# PCBDesign01.net
KiCad netlist of a schematic drawn in EAGLE
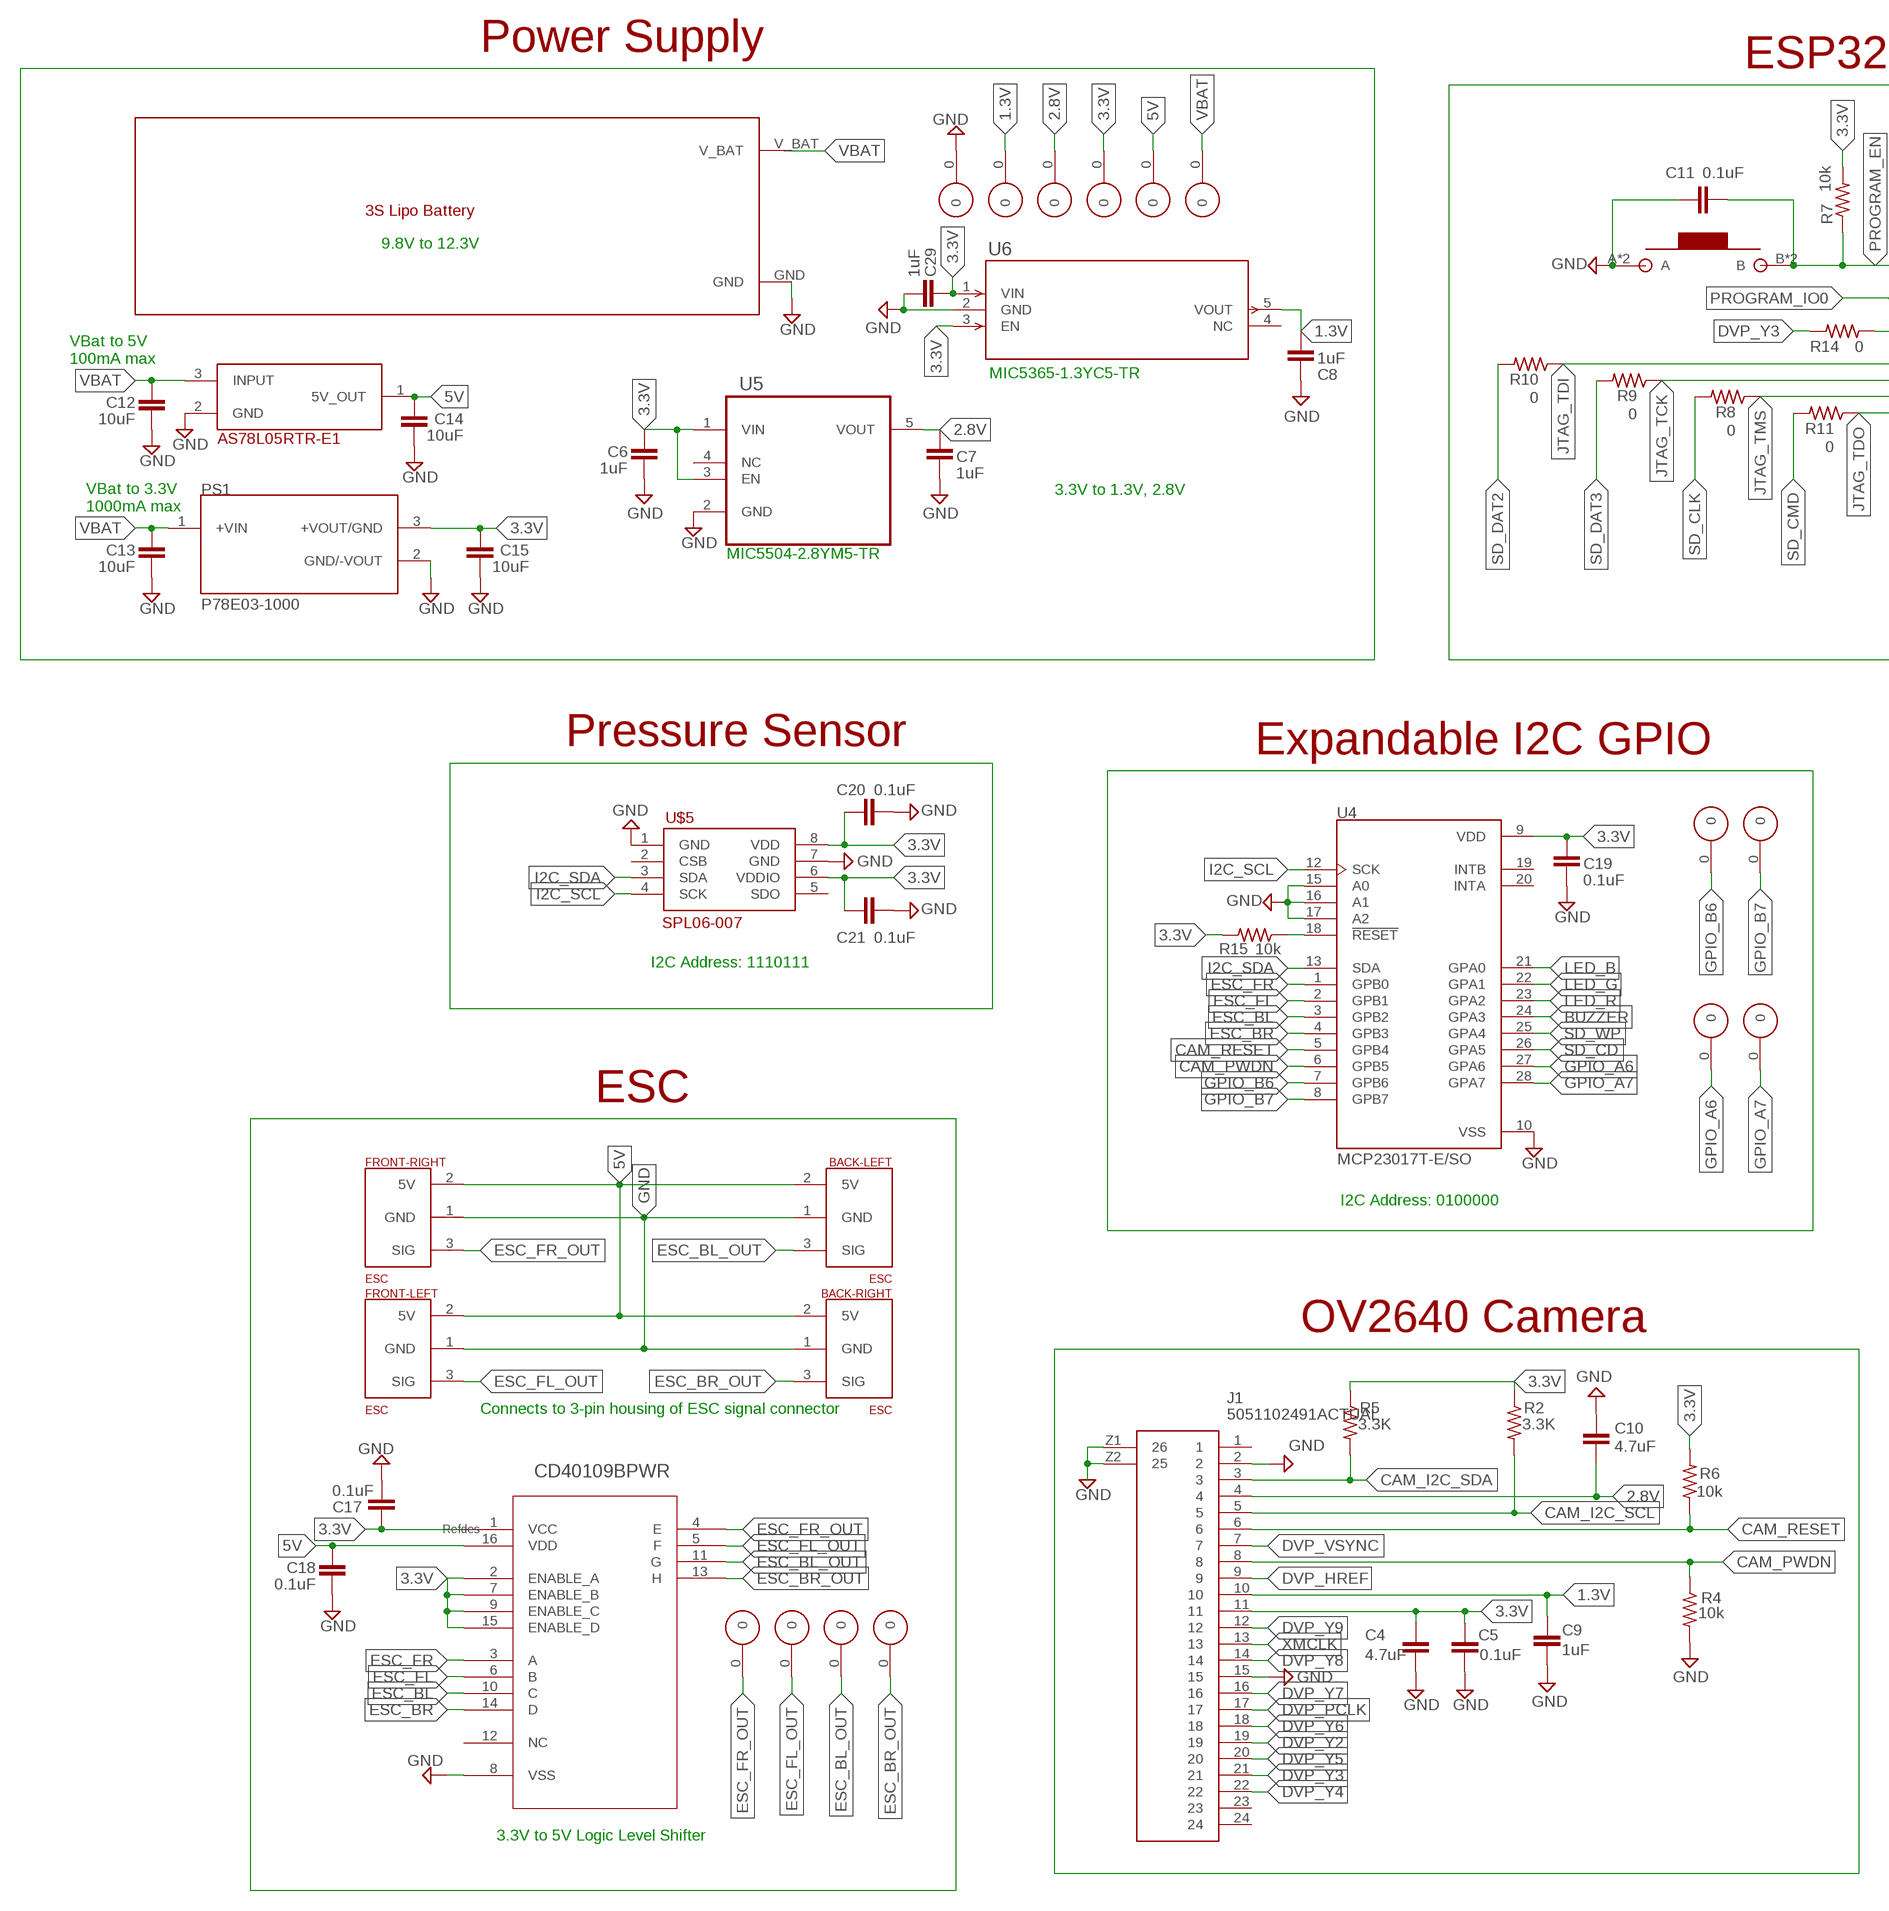
[diagram p0: schematic, sheet 1, part 1 of 2]
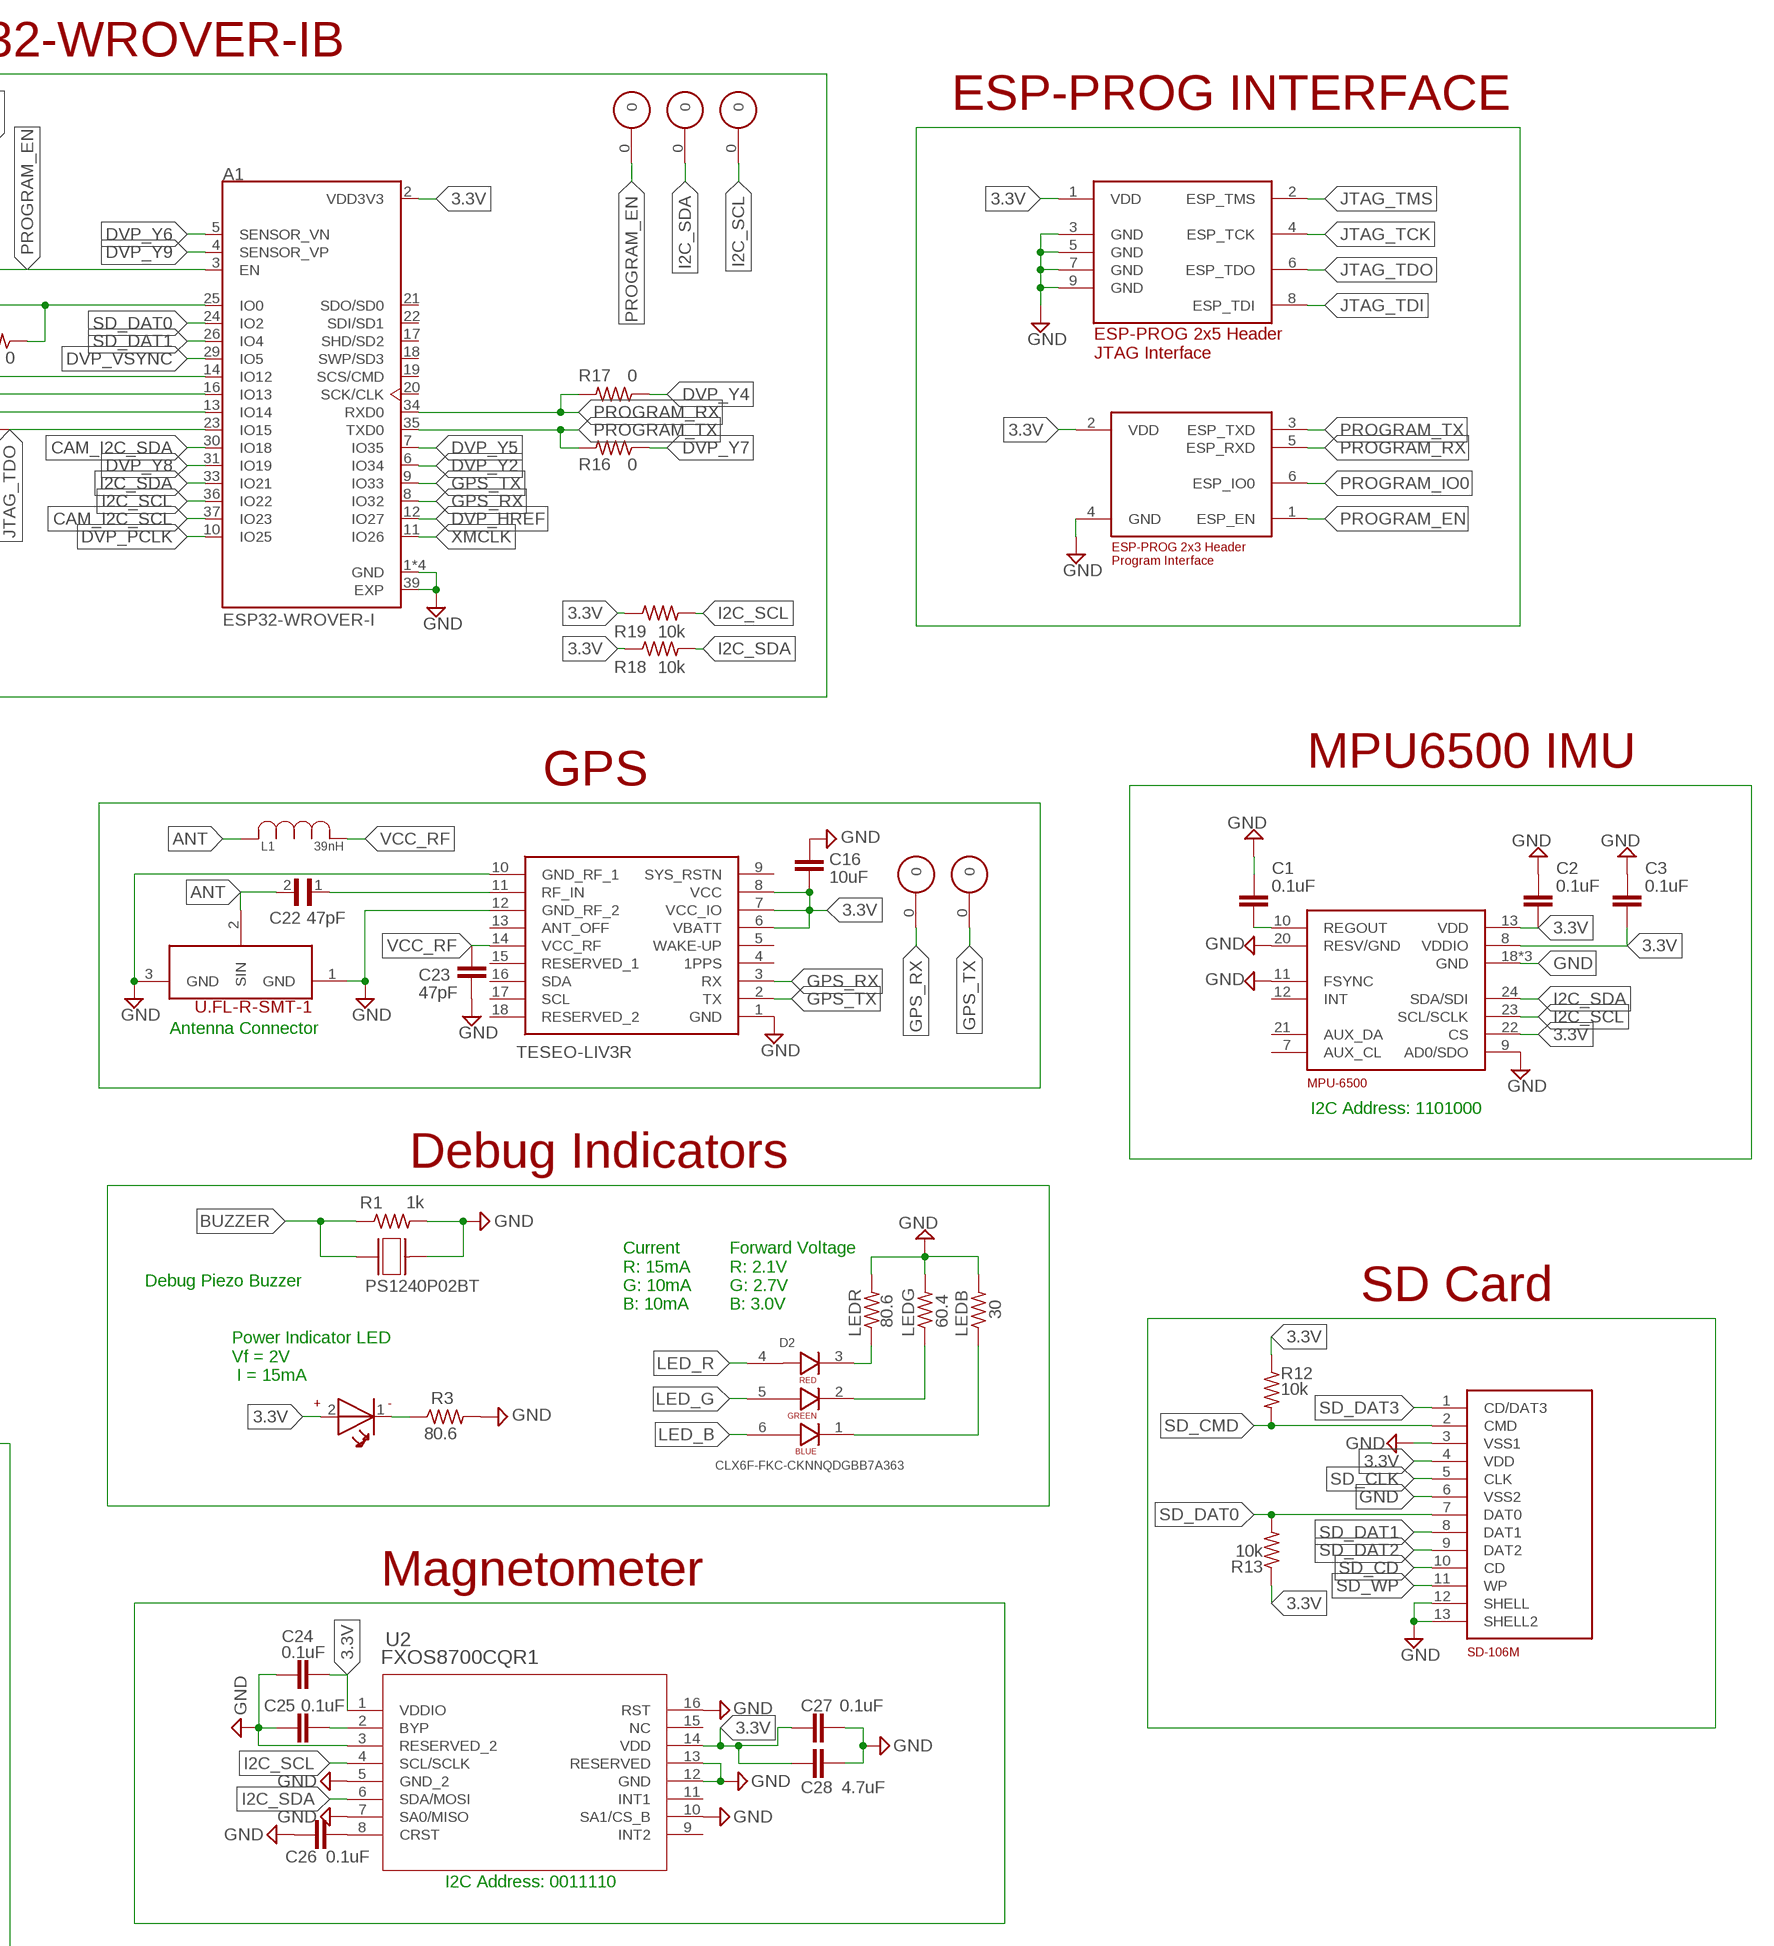
[diagram p1: schematic, sheet 1, part 2 of 2]

(export (version "E")
  (design (tool "Eeschema 10.0.6"))
  (components
    (comp (ref "A1")
      (value "ESP32-WROVER-I")
      (footprint "eagle-import:XCVR_ESP32-WROVER-I")
      (fields (field (name "MF") "Espressif Systems"))
      (libsource (lib "eagle-import") (part "ESP32-WROVER-I"))
    )
    (comp (ref "BACK-LEFT")
      (value "ESC")
      (footprint "eagle-import:MA03-1")
      (libsource (lib "eagle-import") (part "ESC"))
    )
    (comp (ref "BACK-RIGHT")
      (value "ESC")
      (footprint "eagle-import:MA03-1")
      (libsource (lib "eagle-import") (part "ESC"))
    )
    (comp (ref "BUZZER")
      (value "PS1240P02BT")
      (footprint "eagle-import:XDCR_PS1240P02BT")
      (fields (field (name "DIGI-KEY_PART_NUMBER") "445-2525-1-ND") (field (name "MF") "TDK"))
      (libsource (lib "eagle-import") (part "PS1240P02BT"))
    )
    (comp (ref "C1")
      (value "0.1uF")
      (footprint "eagle-import:CAPC2012X110")
      (libsource (lib "eagle-import") (part "CCHIP-0805(2012-METRIC)_"))
    )
    (comp (ref "C2")
      (value "0.1uF")
      (footprint "eagle-import:CAPC2012X110")
      (libsource (lib "eagle-import") (part "CCHIP-0805(2012-METRIC)_"))
    )
    (comp (ref "C3")
      (value "0.1uF")
      (footprint "eagle-import:CAPC2012X110")
      (libsource (lib "eagle-import") (part "CCHIP-0805(2012-METRIC)_"))
    )
    (comp (ref "C4")
      (value "4.7uF")
      (footprint "eagle-import:CAPC2012X110")
      (libsource (lib "eagle-import") (part "CCHIP-0805(2012-METRIC)_"))
    )
    (comp (ref "C5")
      (value "0.1uF")
      (footprint "eagle-import:CAPC2012X110")
      (libsource (lib "eagle-import") (part "CCHIP-0805(2012-METRIC)_"))
    )
    (comp (ref "C6")
      (value "1uF")
      (footprint "eagle-import:CAPC2012X110")
      (libsource (lib "eagle-import") (part "CCHIP-0805(2012-METRIC)_"))
    )
    (comp (ref "C7")
      (value "1uF")
      (footprint "eagle-import:CAPC2012X110")
      (libsource (lib "eagle-import") (part "CCHIP-0805(2012-METRIC)_"))
    )
    (comp (ref "C8")
      (value "1uF")
      (footprint "eagle-import:CAPC2012X110")
      (libsource (lib "eagle-import") (part "CCHIP-0805(2012-METRIC)_"))
    )
    (comp (ref "C9")
      (value "1uF")
      (footprint "eagle-import:CAPC2012X110")
      (libsource (lib "eagle-import") (part "CCHIP-0805(2012-METRIC)_"))
    )
    (comp (ref "C10")
      (value "4.7uF")
      (footprint "eagle-import:CAPC2012X110")
      (libsource (lib "eagle-import") (part "CCHIP-0805(2012-METRIC)_"))
    )
    (comp (ref "C11")
      (value "0.1uF")
      (footprint "eagle-import:CAPC2012X110")
      (libsource (lib "eagle-import") (part "CCHIP-0805(2012-METRIC)_"))
    )
    (comp (ref "C12")
      (value "10uF")
      (footprint "eagle-import:CAPC2012X110")
      (libsource (lib "eagle-import") (part "CCHIP-0805(2012-METRIC)_"))
    )
    (comp (ref "C13")
      (value "10uF")
      (footprint "eagle-import:CAPC2012X110")
      (libsource (lib "eagle-import") (part "CCHIP-0805(2012-METRIC)_"))
    )
    (comp (ref "C14")
      (value "10uF")
      (footprint "eagle-import:CAPC2012X110")
      (libsource (lib "eagle-import") (part "CCHIP-0805(2012-METRIC)_"))
    )
    (comp (ref "C15")
      (value "10uF")
      (footprint "eagle-import:CAPC2012X110")
      (libsource (lib "eagle-import") (part "CCHIP-0805(2012-METRIC)_"))
    )
    (comp (ref "C16")
      (value "10uF")
      (footprint "eagle-import:CAPC2012X110")
      (libsource (lib "eagle-import") (part "CCHIP-0805(2012-METRIC)_"))
    )
    (comp (ref "C17")
      (value "0.1uF")
      (footprint "eagle-import:CAPC2012X110")
      (libsource (lib "eagle-import") (part "CCHIP-0805(2012-METRIC)_"))
    )
    (comp (ref "C18")
      (value "0.1uF")
      (footprint "eagle-import:CAPC2012X110")
      (libsource (lib "eagle-import") (part "CCHIP-0805(2012-METRIC)_"))
    )
    (comp (ref "C19")
      (value "0.1uF")
      (footprint "eagle-import:CAPC2012X110")
      (libsource (lib "eagle-import") (part "CCHIP-0805(2012-METRIC)_"))
    )
    (comp (ref "C20")
      (value "0.1uF")
      (footprint "eagle-import:CAPC2012X110")
      (libsource (lib "eagle-import") (part "CCHIP-0805(2012-METRIC)_"))
    )
    (comp (ref "C21")
      (value "0.1uF")
      (footprint "eagle-import:CAPC2012X110")
      (libsource (lib "eagle-import") (part "CCHIP-0805(2012-METRIC)_"))
    )
    (comp (ref "C22")
      (value "47pF")
      (footprint "eagle-import:CAPC1005X55N")
      (fields
        (field (name "DIGI-KEY_PART_NUMBER") "399-7796-1-ND")
        (field (name "MF") "KEMET")
        (field (name "MP") "C0402C470K5GACTU")
      )
      (libsource (lib "eagle-import") (part "C0402C470K5GACTU"))
    )
    (comp (ref "C23")
      (value "47pF")
      (footprint "eagle-import:CAPC2012X110")
      (libsource (lib "eagle-import") (part "CCHIP-0805(2012-METRIC)_"))
    )
    (comp (ref "C24")
      (value "0.1uF")
      (footprint "eagle-import:CAPC2012X110")
      (libsource (lib "eagle-import") (part "CCHIP-0805(2012-METRIC)_"))
    )
    (comp (ref "C25")
      (value "0.1uF")
      (footprint "eagle-import:CAPC2012X110")
      (libsource (lib "eagle-import") (part "CCHIP-0805(2012-METRIC)_"))
    )
    (comp (ref "C26")
      (value "0.1uF")
      (footprint "eagle-import:CAPC2012X110")
      (libsource (lib "eagle-import") (part "CCHIP-0805(2012-METRIC)_"))
    )
    (comp (ref "C27")
      (value "0.1uF")
      (footprint "eagle-import:CAPC2012X110")
      (libsource (lib "eagle-import") (part "CCHIP-0805(2012-METRIC)_"))
    )
    (comp (ref "C28")
      (value "4.7uF")
      (footprint "eagle-import:CAPC2012X110")
      (libsource (lib "eagle-import") (part "CCHIP-0805(2012-METRIC)_"))
    )
    (comp (ref "C29")
      (value "1uF")
      (footprint "eagle-import:CAPC2012X110")
      (libsource (lib "eagle-import") (part "CCHIP-0805(2012-METRIC)_"))
    )
    (comp (ref "D2")
      (value "CLX6F-FKC-CKNNQDGBB7A363")
      (footprint "eagle-import:SOJ100P350X290-6N")
      (fields (field (name "MF") "Cree Inc."))
      (libsource (lib "eagle-import") (part "CLX6F-FKC-CKNNQDGBB7A363"))
    )
    (comp (ref "FRONT-LEFT")
      (value "ESC")
      (footprint "eagle-import:MA03-1")
      (libsource (lib "eagle-import") (part "ESC"))
    )
    (comp (ref "FRONT-RIGHT")
      (value "ESC")
      (footprint "eagle-import:MA03-1")
      (libsource (lib "eagle-import") (part "ESC"))
    )
    (comp (ref "IC1")
      (value "TESEO-LIV3R")
      (footprint "eagle-import:TESEOLIV3R")
      (fields (field (name "MOUSER_PART_NUMBER") "511-TESEO-LIV3R"))
      (libsource (lib "eagle-import") (part "TESEO-LIV3R"))
    )
    (comp (ref "J1")
      (value "5051102491ACTUAL")
      (footprint "eagle-import:687124149022")
      (libsource (lib "eagle-import") (part "5051102491ACTUAL"))
    )
    (comp (ref "L1")
      (value "39nH")
      (footprint "eagle-import:IND0402_22N_TAI_TAY-M")
      (fields (field (name "MANUFACTURER_PART_NUMBER") "HK100539NJ-T"))
      (libsource (lib "eagle-import") (part "HK100539NJ-TIND0402_22N_TAI_TAY-M"))
    )
    (comp (ref "LEDB")
      (value "30")
      (footprint "eagle-import:RESC2012X65")
      (libsource (lib "eagle-import") (part "R-USCHIP-0805(2012-METRIC)_"))
    )
    (comp (ref "LEDG")
      (value "60.4")
      (footprint "eagle-import:RESC2012X65")
      (libsource (lib "eagle-import") (part "R-USCHIP-0805(2012-METRIC)_"))
    )
    (comp (ref "LEDR")
      (value "80.6")
      (footprint "eagle-import:RESC2012X65")
      (libsource (lib "eagle-import") (part "R-USCHIP-0805(2012-METRIC)_"))
    )
    (comp (ref "PS1")
      (value "P78E03-1000")
      (footprint "eagle-import:CONV_P78E03-1000")
      (fields (field (name "MANUFACTURER") "CUI Inc"))
      (libsource (lib "eagle-import") (part "P78E03-1000"))
    )
    (comp (ref "PWR-INDICATOR")
      (value "WL-SMCW-150060GS75000-G")
      (footprint "eagle-import:WL-SMCW_0603")
      (fields (field (name "MF") "Wurth Electronics") (field (name "MP") "150060VS75000"))
      (libsource (lib "eagle-import") (part "WL-SMCW-150060GS75000-G"))
    )
    (comp (ref "R1")
      (value "1k")
      (footprint "eagle-import:RESC2012X65")
      (libsource (lib "eagle-import") (part "R-USCHIP-0805(2012-METRIC)_"))
    )
    (comp (ref "R2")
      (value "3.3K")
      (footprint "eagle-import:RESC2012X65")
      (libsource (lib "eagle-import") (part "R-USCHIP-0805(2012-METRIC)_"))
    )
    (comp (ref "R3")
      (value "80.6")
      (footprint "eagle-import:RESC2012X65")
      (libsource (lib "eagle-import") (part "R-USCHIP-0805(2012-METRIC)_"))
    )
    (comp (ref "R4")
      (value "10k")
      (footprint "eagle-import:RESC2012X65")
      (libsource (lib "eagle-import") (part "R-USCHIP-0805(2012-METRIC)_"))
    )
    (comp (ref "R5")
      (value "3.3K")
      (footprint "eagle-import:RESC2012X65")
      (libsource (lib "eagle-import") (part "R-USCHIP-0805(2012-METRIC)_"))
    )
    (comp (ref "R6")
      (value "10k")
      (footprint "eagle-import:RESC2012X65")
      (libsource (lib "eagle-import") (part "R-USCHIP-0805(2012-METRIC)_"))
    )
    (comp (ref "R7")
      (value "10k")
      (footprint "eagle-import:RESC2012X65")
      (libsource (lib "eagle-import") (part "R-USCHIP-0805(2012-METRIC)_"))
    )
    (comp (ref "R8")
      (value "0")
      (footprint "eagle-import:RESC2012X65")
      (libsource (lib "eagle-import") (part "R-USCHIP-0805(2012-METRIC)_"))
    )
    (comp (ref "R9")
      (value "0")
      (footprint "eagle-import:RESC2012X65")
      (libsource (lib "eagle-import") (part "R-USCHIP-0805(2012-METRIC)_"))
    )
    (comp (ref "R10")
      (value "0")
      (footprint "eagle-import:RESC2012X65")
      (libsource (lib "eagle-import") (part "R-USCHIP-0805(2012-METRIC)_"))
    )
    (comp (ref "R11")
      (value "0")
      (footprint "eagle-import:RESC2012X65")
      (libsource (lib "eagle-import") (part "R-USCHIP-0805(2012-METRIC)_"))
    )
    (comp (ref "R12")
      (value "10k")
      (footprint "eagle-import:RESC2012X65")
      (libsource (lib "eagle-import") (part "R-USCHIP-0805(2012-METRIC)_"))
    )
    (comp (ref "R13")
      (value "10k")
      (footprint "eagle-import:RESC2012X65")
      (libsource (lib "eagle-import") (part "R-USCHIP-0805(2012-METRIC)_"))
    )
    (comp (ref "R14")
      (value "0")
      (footprint "eagle-import:RESC2012X65")
      (libsource (lib "eagle-import") (part "R-USCHIP-0805(2012-METRIC)_"))
    )
    (comp (ref "R15")
      (value "10k")
      (footprint "eagle-import:RESC2012X65")
      (libsource (lib "eagle-import") (part "R-USCHIP-0805(2012-METRIC)_"))
    )
    (comp (ref "R16")
      (value "0")
      (footprint "eagle-import:RESC2012X65")
      (libsource (lib "eagle-import") (part "R-USCHIP-0805(2012-METRIC)_"))
    )
    (comp (ref "R17")
      (value "0")
      (footprint "eagle-import:RESC2012X65")
      (libsource (lib "eagle-import") (part "R-USCHIP-0805(2012-METRIC)_"))
    )
    (comp (ref "R18")
      (value "10k")
      (footprint "eagle-import:RESC2012X65")
      (libsource (lib "eagle-import") (part "R-USCHIP-0805(2012-METRIC)_"))
    )
    (comp (ref "R19")
      (value "10k")
      (footprint "eagle-import:RESC2012X65")
      (libsource (lib "eagle-import") (part "R-USCHIP-0805(2012-METRIC)_"))
    )
    (comp (ref "U$1")
      (value "MPU6500")
      (footprint "eagle-import:QFN40P300X300X105-24N")
      (libsource (lib "eagle-import") (part "MPU6500"))
    )
    (comp (ref "U$2")
      (value "TESTPOINT")
      (footprint "eagle-import:TESTPOINT")
      (libsource (lib "eagle-import") (part "TESTPOINT"))
    )
    (comp (ref "U$3")
      (value "SD-106M")
      (footprint "eagle-import:SDCARD")
      (libsource (lib "eagle-import") (part "SD-106M"))
    )
    (comp (ref "U$4")
      (value "U.FL-R-SMT-1")
      (footprint "eagle-import:U.FL")
      (libsource (lib "eagle-import") (part "U.FL-R-SMT-1"))
    )
    (comp (ref "U$5")
      (value "SPL06-007")
      (footprint "eagle-import:SPL06-007")
      (libsource (lib "eagle-import") (part "SPL06-007"))
    )
    (comp (ref "U$6")
      (value "ESP-PROG_JTAG_HEADER")
      (footprint "eagle-import:SAMTEC-FTS-105-01-X-D")
      (libsource (lib "eagle-import") (part "ESP-PROG_JTAG_HEADER"))
    )
    (comp (ref "U$7")
      (value "ESP-PROG_PROGRAM_HEADER")
      (footprint "eagle-import:SAMTEC-FTS-103-01-X-D")
      (libsource (lib "eagle-import") (part "ESP-PROG_PROGRAM_HEADER"))
    )
    (comp (ref "U$8")
      (value "RESET")
      (footprint "eagle-import:BUTTON")
      (libsource (lib "eagle-import") (part "BUTTON"))
    )
    (comp (ref "U$9")
      (value "TESTPOINT")
      (footprint "eagle-import:TESTPOINT")
      (libsource (lib "eagle-import") (part "TESTPOINT"))
    )
    (comp (ref "U$10")
      (value "TESTPOINT")
      (footprint "eagle-import:TESTPOINT")
      (libsource (lib "eagle-import") (part "TESTPOINT"))
    )
    (comp (ref "U$11")
      (value "TESTPOINT")
      (footprint "eagle-import:TESTPOINT")
      (libsource (lib "eagle-import") (part "TESTPOINT"))
    )
    (comp (ref "U$12")
      (value "TESTPOINT")
      (footprint "eagle-import:TESTPOINT")
      (libsource (lib "eagle-import") (part "TESTPOINT"))
    )
    (comp (ref "U$13")
      (value "TESTPOINT")
      (footprint "eagle-import:TESTPOINT")
      (libsource (lib "eagle-import") (part "TESTPOINT"))
    )
    (comp (ref "U$14")
      (value "TESTPOINT")
      (footprint "eagle-import:TESTPOINT")
      (libsource (lib "eagle-import") (part "TESTPOINT"))
    )
    (comp (ref "U$15")
      (value "TESTPOINT")
      (footprint "eagle-import:TESTPOINT")
      (libsource (lib "eagle-import") (part "TESTPOINT"))
    )
    (comp (ref "U$16")
      (value "TESTPOINT")
      (footprint "eagle-import:TESTPOINT")
      (libsource (lib "eagle-import") (part "TESTPOINT"))
    )
    (comp (ref "U$17")
      (value "TESTPOINT")
      (footprint "eagle-import:TESTPOINT")
      (libsource (lib "eagle-import") (part "TESTPOINT"))
    )
    (comp (ref "U$18")
      (value "TESTPOINT")
      (footprint "eagle-import:TESTPOINT")
      (libsource (lib "eagle-import") (part "TESTPOINT"))
    )
    (comp (ref "U$19")
      (value "TESTPOINT")
      (footprint "eagle-import:TESTPOINT")
      (libsource (lib "eagle-import") (part "TESTPOINT"))
    )
    (comp (ref "U$20")
      (value "TESTPOINT")
      (footprint "eagle-import:TESTPOINT")
      (libsource (lib "eagle-import") (part "TESTPOINT"))
    )
    (comp (ref "U$21")
      (value "TESTPOINT")
      (footprint "eagle-import:TESTPOINT")
      (libsource (lib "eagle-import") (part "TESTPOINT"))
    )
    (comp (ref "U$23")
      (value "TESTPOINT")
      (footprint "eagle-import:TESTPOINT")
      (libsource (lib "eagle-import") (part "TESTPOINT"))
    )
    (comp (ref "U$24")
      (value "TESTPOINT")
      (footprint "eagle-import:TESTPOINT")
      (libsource (lib "eagle-import") (part "TESTPOINT"))
    )
    (comp (ref "U$25")
      (value "TESTPOINT")
      (footprint "eagle-import:TESTPOINT")
      (libsource (lib "eagle-import") (part "TESTPOINT"))
    )
    (comp (ref "U$26")
      (value "TESTPOINT")
      (footprint "eagle-import:TESTPOINT")
      (libsource (lib "eagle-import") (part "TESTPOINT"))
    )
    (comp (ref "U$27")
      (value "TESTPOINT")
      (footprint "eagle-import:TESTPOINT")
      (libsource (lib "eagle-import") (part "TESTPOINT"))
    )
    (comp (ref "U$28")
      (value "AS78L05RTR-E1")
      (footprint "eagle-import:VREG_AP2204RA-3.3TRG1")
      (libsource (lib "eagle-import") (part "AS78L05RTR-E1"))
    )
    (comp (ref "U$29")
      (value "LARGE_BATTERY")
      (footprint "eagle-import:LARGE_BATTERY")
      (libsource (lib "eagle-import") (part "LARGE_BATTERY"))
    )
    (comp (ref "U2")
      (value "FXOS8700CQR1")
      (footprint "eagle-import:QFN16_3X3_NXP")
      (fields (field (name "COPYRIGHT") "Copyright (C) 2018 Accelerated Designs. All rights reserved"))
      (libsource (lib "eagle-import") (part "FXOS8700CQR1"))
    )
    (comp (ref "U3")
      (value "CD40109BPWR")
      (footprint "eagle-import:SOP65P640X120-16N")
      (fields (field (name "DIGI-KEY_PART_NUMBER") "296-12163-1-ND") (field (name "MF") "Texas Instruments"))
      (libsource (lib "eagle-import") (part "CD40109BPWR"))
    )
    (comp (ref "U4")
      (value "MCP23017T-E/SO")
      (footprint "eagle-import:SOIC127P1030X265-28N")
      (fields (field (name "DIGI-KEY_PART_NUMBER") "MCP23017T-E/SOCT-ND") (field (name "MF") "Microchip"))
      (libsource (lib "eagle-import") (part "MCP23017T-E/SO"))
    )
    (comp (ref "U5")
      (value "MIC5504-2.8YM5-TR")
      (footprint "eagle-import:SOT95P280X145-5N")
      (fields (field (name "MF") "Texas Instruments") (field (name "MP") "TPS61097-33DBVR"))
      (libsource (lib "eagle-import") (part "MIC5504-2.8YM5-TR"))
    )
    (comp (ref "U6")
      (value "MIC5365-1.3YC5-TRSC-70_C5_MCH-M")
      (footprint "eagle-import:SC-70_C5_MCH-M")
      (fields
        (field (name "MANUFACTURER_PART_NUMBER") "MIC5365-1.3YC5-TR")
        (field (name "COPYRIGHT") "Copyright (C) 2018 Accelerated Designs. All rights reserved")
      )
      (libsource (lib "eagle-import") (part "MIC5365-1.3YC5-TRSC-70_C5_MCH-M"))
    )
  )
  (nets
    (net (code "1") (name "1.3V") (class "Default")
      (node (ref "C8") (pin "1") (pinfunction "1_1") (pintype "passive"))
      (node (ref "C9") (pin "2") (pinfunction "2_2") (pintype "passive"))
      (node (ref "J1") (pin "10") (pinfunction "10_10") (pintype "bidirectional"))
      (node (ref "U$17") (pin "0") (pinfunction "0_0") (pintype "bidirectional"))
      (node (ref "U6") (pin "5") (pinfunction "VOUT_5") (pintype "output"))
    )
    (net (code "2") (name "2.8V") (class "Default")
      (node (ref "C10") (pin "1") (pinfunction "1_1") (pintype "passive"))
      (node (ref "C7") (pin "1") (pinfunction "1_1") (pintype "passive"))
      (node (ref "J1") (pin "4") (pinfunction "4_4") (pintype "bidirectional"))
      (node (ref "U$18") (pin "0") (pinfunction "0_0") (pintype "bidirectional"))
      (node (ref "U5") (pin "5") (pinfunction "VOUT_5") (pintype "output"))
    )
    (net (code "3") (name "3.3V") (class "Default")
      (node (ref "A1") (pin "2") (pinfunction "VDD3V3_2") (pintype "power_in"))
      (node (ref "C15") (pin "2") (pinfunction "2_2") (pintype "passive"))
      (node (ref "C16") (pin "2") (pinfunction "2_2") (pintype "passive"))
      (node (ref "C17") (pin "2") (pinfunction "2_2") (pintype "passive"))
      (node (ref "C19") (pin "2") (pinfunction "2_2") (pintype "passive"))
      (node (ref "C2") (pin "2") (pinfunction "2_2") (pintype "passive"))
      (node (ref "C20") (pin "2") (pinfunction "2_2") (pintype "passive"))
      (node (ref "C21") (pin "2") (pinfunction "2_2") (pintype "passive"))
      (node (ref "C24") (pin "2") (pinfunction "2_2") (pintype "passive"))
      (node (ref "C27") (pin "1") (pinfunction "1_1") (pintype "passive"))
      (node (ref "C28") (pin "1") (pinfunction "1_1") (pintype "passive"))
      (node (ref "C29") (pin "1") (pinfunction "1_1") (pintype "passive"))
      (node (ref "C3") (pin "2") (pinfunction "2_2") (pintype "passive"))
      (node (ref "C4") (pin "1") (pinfunction "1_1") (pintype "passive"))
      (node (ref "C5") (pin "1") (pinfunction "1_1") (pintype "passive"))
      (node (ref "C6") (pin "1") (pinfunction "1_1") (pintype "passive"))
      (node (ref "IC1") (pin "6") (pinfunction "VBATT_6") (pintype "bidirectional"))
      (node (ref "IC1") (pin "7") (pinfunction "VCC_IO_7") (pintype "bidirectional"))
      (node (ref "IC1") (pin "8") (pinfunction "VCC_8") (pintype "bidirectional"))
      (node (ref "J1") (pin "11") (pinfunction "11_11") (pintype "bidirectional"))
      (node (ref "PS1") (pin "3") (pinfunction "+VOUT/GND_3") (pintype "power_in"))
      (node (ref "PWR-INDICATOR") (pin "2") (pinfunction "+_2") (pintype "bidirectional"))
      (node (ref "R12") (pin "1") (pinfunction "1_1") (pintype "passive"))
      (node (ref "R13") (pin "1") (pinfunction "1_1") (pintype "passive"))
      (node (ref "R15") (pin "2") (pinfunction "2_2") (pintype "passive"))
      (node (ref "R18") (pin "1") (pinfunction "1_1") (pintype "passive"))
      (node (ref "R19") (pin "1") (pinfunction "1_1") (pintype "passive"))
      (node (ref "R2") (pin "1") (pinfunction "1_1") (pintype "passive"))
      (node (ref "R5") (pin "1") (pinfunction "1_1") (pintype "passive"))
      (node (ref "R6") (pin "2") (pinfunction "2_2") (pintype "passive"))
      (node (ref "R7") (pin "2") (pinfunction "2_2") (pintype "passive"))
      (node (ref "U$1") (pin "13") (pinfunction "VDD_13") (pintype "bidirectional"))
      (node (ref "U$1") (pin "22") (pinfunction "CS_22") (pintype "bidirectional"))
      (node (ref "U$1") (pin "8") (pinfunction "VDDIO_8") (pintype "bidirectional"))
      (node (ref "U$15") (pin "0") (pinfunction "0_0") (pintype "bidirectional"))
      (node (ref "U$3") (pin "4") (pinfunction "VDD_4") (pintype "bidirectional"))
      (node (ref "U$5") (pin "6") (pinfunction "VDDIO_6") (pintype "bidirectional"))
      (node (ref "U$5") (pin "8") (pinfunction "VDD_8") (pintype "bidirectional"))
      (node (ref "U$6") (pin "1") (pinfunction "VDD_1") (pintype "bidirectional"))
      (node (ref "U$7") (pin "2") (pinfunction "VDD_2") (pintype "bidirectional"))
      (node (ref "U2") (pin "1") (pinfunction "VDDIO_1") (pintype "power_in"))
      (node (ref "U2") (pin "14") (pinfunction "VDD_14") (pintype "power_in"))
      (node (ref "U3") (pin "1") (pinfunction "VCC_1") (pintype "power_in"))
      (node (ref "U3") (pin "15") (pinfunction "ENABLE_D_15") (pintype "input"))
      (node (ref "U3") (pin "2") (pinfunction "ENABLE_A_2") (pintype "input"))
      (node (ref "U3") (pin "7") (pinfunction "ENABLE_B_7") (pintype "input"))
      (node (ref "U3") (pin "9") (pinfunction "ENABLE_C_9") (pintype "input"))
      (node (ref "U4") (pin "9") (pinfunction "VDD_9") (pintype "power_in"))
      (node (ref "U5") (pin "1") (pinfunction "VIN_1") (pintype "power_in"))
      (node (ref "U5") (pin "3") (pinfunction "EN_3") (pintype "input"))
      (node (ref "U6") (pin "1") (pinfunction "VIN_1") (pintype "input"))
      (node (ref "U6") (pin "3") (pinfunction "EN_3") (pintype "input"))
    )
    (net (code "4") (name "5V") (class "Default")
      (node (ref "BACK-LEFT") (pin "2") (pinfunction "5V_2") (pintype "bidirectional"))
      (node (ref "BACK-RIGHT") (pin "2") (pinfunction "5V_2") (pintype "bidirectional"))
      (node (ref "C14") (pin "2") (pinfunction "2_2") (pintype "passive"))
      (node (ref "C18") (pin "2") (pinfunction "2_2") (pintype "passive"))
      (node (ref "FRONT-LEFT") (pin "2") (pinfunction "5V_2") (pintype "bidirectional"))
      (node (ref "FRONT-RIGHT") (pin "2") (pinfunction "5V_2") (pintype "bidirectional"))
      (node (ref "U$16") (pin "0") (pinfunction "0_0") (pintype "bidirectional"))
      (node (ref "U$28") (pin "1") (pinfunction "5V_OUT_1") (pintype "bidirectional"))
      (node (ref "U3") (pin "16") (pinfunction "VDD_16") (pintype "power_in"))
    )
    (net (code "5") (name "ANT") (class "Default")
      (node (ref "C22") (pin "2") (pinfunction "2_2") (pintype "passive"))
      (node (ref "L1") (pin "2") (pinfunction "2_2") (pintype "passive"))
      (node (ref "U$4") (pin "2") (pinfunction "SIN_2") (pintype "bidirectional"))
    )
    (net (code "6") (name "BUZZER") (class "Default")
      (node (ref "BUZZER") (pin "1") (pinfunction "1_1") (pintype "passive"))
      (node (ref "R1") (pin "1") (pinfunction "1_1") (pintype "passive"))
      (node (ref "U4") (pin "24") (pinfunction "GPA3_24") (pintype "bidirectional"))
    )
    (net (code "7") (name "CAM_I2C_SCL") (class "Default")
      (node (ref "A1") (pin "37") (pinfunction "IO23_37") (pintype "bidirectional"))
      (node (ref "J1") (pin "5") (pinfunction "5_5") (pintype "bidirectional"))
      (node (ref "R2") (pin "2") (pinfunction "2_2") (pintype "passive"))
    )
    (net (code "8") (name "CAM_I2C_SDA") (class "Default")
      (node (ref "A1") (pin "30") (pinfunction "IO18_30") (pintype "bidirectional"))
      (node (ref "J1") (pin "3") (pinfunction "3_3") (pintype "bidirectional"))
      (node (ref "R5") (pin "2") (pinfunction "2_2") (pintype "passive"))
    )
    (net (code "9") (name "CAM_PWDN") (class "Default")
      (node (ref "J1") (pin "8") (pinfunction "8_8") (pintype "bidirectional"))
      (node (ref "R4") (pin "1") (pinfunction "1_1") (pintype "passive"))
      (node (ref "U4") (pin "6") (pinfunction "GPB5_6") (pintype "bidirectional"))
    )
    (net (code "10") (name "CAM_RESET") (class "Default")
      (node (ref "J1") (pin "6") (pinfunction "6_6") (pintype "bidirectional"))
      (node (ref "R6") (pin "1") (pinfunction "1_1") (pintype "passive"))
      (node (ref "U4") (pin "5") (pinfunction "GPB4_5") (pintype "bidirectional"))
    )
    (net (code "11") (name "DVP_HREF") (class "Default")
      (node (ref "A1") (pin "12") (pinfunction "IO27_12") (pintype "bidirectional"))
      (node (ref "J1") (pin "9") (pinfunction "9_9") (pintype "bidirectional"))
    )
    (net (code "12") (name "DVP_PCLK") (class "Default")
      (node (ref "A1") (pin "10") (pinfunction "IO25_10") (pintype "bidirectional"))
      (node (ref "J1") (pin "17") (pinfunction "17_17") (pintype "bidirectional"))
    )
    (net (code "13") (name "DVP_VSYNC") (class "Default")
      (node (ref "A1") (pin "29") (pinfunction "IO5_29") (pintype "bidirectional"))
      (node (ref "J1") (pin "7") (pinfunction "7_7") (pintype "bidirectional"))
    )
    (net (code "14") (name "DVP_Y2") (class "Default")
      (node (ref "A1") (pin "6") (pinfunction "IO34_6") (pintype "input"))
      (node (ref "J1") (pin "19") (pinfunction "19_19") (pintype "bidirectional"))
    )
    (net (code "15") (name "DVP_Y3") (class "Default")
      (node (ref "J1") (pin "21") (pinfunction "21_21") (pintype "bidirectional"))
      (node (ref "R14") (pin "2") (pinfunction "2_2") (pintype "passive"))
    )
    (net (code "16") (name "DVP_Y4") (class "Default")
      (node (ref "J1") (pin "22") (pinfunction "22_22") (pintype "bidirectional"))
      (node (ref "R17") (pin "1") (pinfunction "1_1") (pintype "passive"))
    )
    (net (code "17") (name "DVP_Y5") (class "Default")
      (node (ref "A1") (pin "7") (pinfunction "IO35_7") (pintype "input"))
      (node (ref "J1") (pin "20") (pinfunction "20_20") (pintype "bidirectional"))
    )
    (net (code "18") (name "DVP_Y6") (class "Default")
      (node (ref "A1") (pin "5") (pinfunction "SENSOR_VN_5") (pintype "input"))
      (node (ref "J1") (pin "18") (pinfunction "18_18") (pintype "bidirectional"))
    )
    (net (code "19") (name "DVP_Y7") (class "Default")
      (node (ref "J1") (pin "16") (pinfunction "16_16") (pintype "bidirectional"))
      (node (ref "R16") (pin "1") (pinfunction "1_1") (pintype "passive"))
    )
    (net (code "20") (name "DVP_Y8") (class "Default")
      (node (ref "A1") (pin "31") (pinfunction "IO19_31") (pintype "bidirectional"))
      (node (ref "J1") (pin "14") (pinfunction "14_14") (pintype "bidirectional"))
    )
    (net (code "21") (name "DVP_Y9") (class "Default")
      (node (ref "A1") (pin "4") (pinfunction "SENSOR_VP_4") (pintype "input"))
      (node (ref "J1") (pin "12") (pinfunction "12_12") (pintype "bidirectional"))
    )
    (net (code "22") (name "ESC_BL") (class "Default")
      (node (ref "U3") (pin "10") (pinfunction "C_10") (pintype "input"))
      (node (ref "U4") (pin "3") (pinfunction "GPB2_3") (pintype "bidirectional"))
    )
    (net (code "23") (name "ESC_BL_OUT") (class "Default")
      (node (ref "BACK-LEFT") (pin "3") (pinfunction "SIG_3") (pintype "bidirectional"))
      (node (ref "U$25") (pin "0") (pinfunction "0_0") (pintype "bidirectional"))
      (node (ref "U3") (pin "11") (pinfunction "G_11") (pintype "output"))
    )
    (net (code "24") (name "ESC_BR") (class "Default")
      (node (ref "U3") (pin "14") (pinfunction "D_14") (pintype "input"))
      (node (ref "U4") (pin "4") (pinfunction "GPB3_4") (pintype "bidirectional"))
    )
    (net (code "25") (name "ESC_BR_OUT") (class "Default")
      (node (ref "BACK-RIGHT") (pin "3") (pinfunction "SIG_3") (pintype "bidirectional"))
      (node (ref "U$27") (pin "0") (pinfunction "0_0") (pintype "bidirectional"))
      (node (ref "U3") (pin "13") (pinfunction "H_13") (pintype "output"))
    )
    (net (code "26") (name "ESC_FL") (class "Default")
      (node (ref "U3") (pin "6") (pinfunction "B_6") (pintype "input"))
      (node (ref "U4") (pin "2") (pinfunction "GPB1_2") (pintype "bidirectional"))
    )
    (net (code "27") (name "ESC_FL_OUT") (class "Default")
      (node (ref "FRONT-LEFT") (pin "3") (pinfunction "SIG_3") (pintype "bidirectional"))
      (node (ref "U$26") (pin "0") (pinfunction "0_0") (pintype "bidirectional"))
      (node (ref "U3") (pin "5") (pinfunction "F_5") (pintype "output"))
    )
    (net (code "28") (name "ESC_FR") (class "Default")
      (node (ref "U3") (pin "3") (pinfunction "A_3") (pintype "input"))
      (node (ref "U4") (pin "1") (pinfunction "GPB0_1") (pintype "bidirectional"))
    )
    (net (code "29") (name "ESC_FR_OUT") (class "Default")
      (node (ref "FRONT-RIGHT") (pin "3") (pinfunction "SIG_3") (pintype "bidirectional"))
      (node (ref "U$24") (pin "0") (pinfunction "0_0") (pintype "bidirectional"))
      (node (ref "U3") (pin "4") (pinfunction "E_4") (pintype "output"))
    )
    (net (code "30") (name "GND") (class "Default")
      (node (ref "A1") (pin "1") (pinfunction "GND_1") (pintype "power_in"))
      (node (ref "A1") (pin "15") (pinfunction "GND_15") (pintype "power_in"))
      (node (ref "A1") (pin "38") (pinfunction "GND_38") (pintype "power_in"))
      (node (ref "A1") (pin "39") (pinfunction "EXP_39") (pintype "power_in"))
      (node (ref "A1") (pin "P$1") (pinfunction "GND_P$1") (pintype "power_in"))
      (node (ref "BACK-LEFT") (pin "1") (pinfunction "GND_1") (pintype "bidirectional"))
      (node (ref "BACK-RIGHT") (pin "1") (pinfunction "GND_1") (pintype "bidirectional"))
      (node (ref "BUZZER") (pin "2") (pinfunction "2_2") (pintype "passive"))
      (node (ref "C1") (pin "1") (pinfunction "1_1") (pintype "passive"))
      (node (ref "C10") (pin "2") (pinfunction "2_2") (pintype "passive"))
      (node (ref "C11") (pin "1") (pinfunction "1_1") (pintype "passive"))
      (node (ref "C12") (pin "1") (pinfunction "1_1") (pintype "passive"))
      (node (ref "C13") (pin "1") (pinfunction "1_1") (pintype "passive"))
      (node (ref "C14") (pin "1") (pinfunction "1_1") (pintype "passive"))
      (node (ref "C15") (pin "1") (pinfunction "1_1") (pintype "passive"))
      (node (ref "C16") (pin "1") (pinfunction "1_1") (pintype "passive"))
      (node (ref "C17") (pin "1") (pinfunction "1_1") (pintype "passive"))
      (node (ref "C18") (pin "1") (pinfunction "1_1") (pintype "passive"))
      (node (ref "C19") (pin "1") (pinfunction "1_1") (pintype "passive"))
      (node (ref "C2") (pin "1") (pinfunction "1_1") (pintype "passive"))
      (node (ref "C20") (pin "1") (pinfunction "1_1") (pintype "passive"))
      (node (ref "C21") (pin "1") (pinfunction "1_1") (pintype "passive"))
      (node (ref "C23") (pin "1") (pinfunction "1_1") (pintype "passive"))
      (node (ref "C24") (pin "1") (pinfunction "1_1") (pintype "passive"))
      (node (ref "C25") (pin "2") (pinfunction "2_2") (pintype "passive"))
      (node (ref "C26") (pin "2") (pinfunction "2_2") (pintype "passive"))
      (node (ref "C27") (pin "2") (pinfunction "2_2") (pintype "passive"))
      (node (ref "C28") (pin "2") (pinfunction "2_2") (pintype "passive"))
      (node (ref "C29") (pin "2") (pinfunction "2_2") (pintype "passive"))
      (node (ref "C3") (pin "1") (pinfunction "1_1") (pintype "passive"))
      (node (ref "C4") (pin "2") (pinfunction "2_2") (pintype "passive"))
      (node (ref "C5") (pin "2") (pinfunction "2_2") (pintype "passive"))
      (node (ref "C6") (pin "2") (pinfunction "2_2") (pintype "passive"))
      (node (ref "C7") (pin "2") (pinfunction "2_2") (pintype "passive"))
      (node (ref "C8") (pin "2") (pinfunction "2_2") (pintype "passive"))
      (node (ref "C9") (pin "1") (pinfunction "1_1") (pintype "passive"))
      (node (ref "FRONT-LEFT") (pin "1") (pinfunction "GND_1") (pintype "bidirectional"))
      (node (ref "FRONT-RIGHT") (pin "1") (pinfunction "GND_1") (pintype "bidirectional"))
      (node (ref "IC1") (pin "1") (pinfunction "GND_1") (pintype "bidirectional"))
      (node (ref "IC1") (pin "10") (pinfunction "GND_RF_1_10") (pintype "bidirectional"))
      (node (ref "IC1") (pin "12") (pinfunction "GND_RF_2_12") (pintype "bidirectional"))
      (node (ref "J1") (pin "15") (pinfunction "15_15") (pintype "bidirectional"))
      (node (ref "J1") (pin "2") (pinfunction "2_2") (pintype "bidirectional"))
      (node (ref "J1") (pin "Z1") (pinfunction "26_Z1") (pintype "bidirectional"))
      (node (ref "J1") (pin "Z2") (pinfunction "25_Z2") (pintype "bidirectional"))
      (node (ref "LEDB") (pin "2") (pinfunction "2_2") (pintype "passive"))
      (node (ref "LEDG") (pin "2") (pinfunction "2_2") (pintype "passive"))
      (node (ref "LEDR") (pin "2") (pinfunction "2_2") (pintype "passive"))
      (node (ref "PS1") (pin "2") (pinfunction "GND/-VOUT_2") (pintype "power_in"))
      (node (ref "R1") (pin "2") (pinfunction "2_2") (pintype "passive"))
      (node (ref "R3") (pin "2") (pinfunction "2_2") (pintype "passive"))
      (node (ref "R4") (pin "2") (pinfunction "2_2") (pintype "passive"))
      (node (ref "U$1") (pin "11") (pinfunction "FSYNC_11") (pintype "bidirectional"))
      (node (ref "U$1") (pin "18") (pinfunction "GND_18") (pintype "bidirectional"))
      (node (ref "U$1") (pin "20") (pinfunction "RESV/GND_20") (pintype "bidirectional"))
      (node (ref "U$1") (pin "25") (pinfunction "GND_25") (pintype "bidirectional"))
      (node (ref "U$1") (pin "9") (pinfunction "AD0/SDO_9") (pintype "bidirectional"))
      (node (ref "U$1") (pin "P$1") (pinfunction "GND_P$1") (pintype "bidirectional"))
      (node (ref "U$21") (pin "0") (pinfunction "0_0") (pintype "bidirectional"))
      (node (ref "U$28") (pin "2") (pinfunction "GND_2") (pintype "bidirectional"))
      (node (ref "U$29") (pin "GND") (pinfunction "GND_GND") (pintype "bidirectional"))
      (node (ref "U$3") (pin "12") (pinfunction "SHELL_12") (pintype "bidirectional"))
      (node (ref "U$3") (pin "13") (pinfunction "SHELL2_13") (pintype "bidirectional"))
      (node (ref "U$3") (pin "3") (pinfunction "VSS1_3") (pintype "bidirectional"))
      (node (ref "U$3") (pin "6") (pinfunction "VSS2_6") (pintype "bidirectional"))
      (node (ref "U$4") (pin "1") (pinfunction "GND_1") (pintype "bidirectional"))
      (node (ref "U$4") (pin "3") (pinfunction "GND_3") (pintype "bidirectional"))
      (node (ref "U$5") (pin "1") (pinfunction "GND_1") (pintype "bidirectional"))
      (node (ref "U$5") (pin "7") (pinfunction "GND_7") (pintype "bidirectional"))
      (node (ref "U$6") (pin "3") (pinfunction "GND_3") (pintype "bidirectional"))
      (node (ref "U$6") (pin "5") (pinfunction "GND_5") (pintype "bidirectional"))
      (node (ref "U$6") (pin "7") (pinfunction "GND_7") (pintype "bidirectional"))
      (node (ref "U$6") (pin "9") (pinfunction "GND_9") (pintype "bidirectional"))
      (node (ref "U$7") (pin "4") (pinfunction "GND_4") (pintype "bidirectional"))
      (node (ref "U$8") (pin "A") (pinfunction "A_A") (pintype "bidirectional"))
      (node (ref "U$8") (pin "A@1") (pinfunction "A_A@1") (pintype "bidirectional"))
      (node (ref "U2") (pin "10") (pinfunction "SA1/CS_B_10") (pintype "bidirectional"))
      (node (ref "U2") (pin "12") (pinfunction "GND_12") (pintype "power_in"))
      (node (ref "U2") (pin "13") (pinfunction "RESERVED_13") (pintype "passive"))
      (node (ref "U2") (pin "16") (pinfunction "RST_16") (pintype "input"))
      (node (ref "U2") (pin "3") (pinfunction "RESERVED_2_3") (pintype "passive"))
      (node (ref "U2") (pin "5") (pinfunction "GND_2_5") (pintype "power_in"))
      (node (ref "U2") (pin "7") (pinfunction "SA0/MISO_7") (pintype "bidirectional"))
      (node (ref "U3") (pin "8") (pinfunction "VSS_8") (pintype "input"))
      (node (ref "U4") (pin "10") (pinfunction "VSS_10") (pintype "power_in"))
      (node (ref "U4") (pin "15") (pinfunction "A0_15") (pintype "input"))
      (node (ref "U4") (pin "16") (pinfunction "A1_16") (pintype "input"))
      (node (ref "U4") (pin "17") (pinfunction "A2_17") (pintype "input"))
      (node (ref "U5") (pin "2") (pinfunction "GND_2") (pintype "passive"))
      (node (ref "U6") (pin "2") (pinfunction "GND_2") (pintype "power_in"))
    )
    (net (code "31") (name "GPIO_A6") (class "Default")
      (node (ref "U$2") (pin "0") (pinfunction "0_0") (pintype "bidirectional"))
      (node (ref "U4") (pin "27") (pinfunction "GPA6_27") (pintype "bidirectional"))
    )
    (net (code "32") (name "GPIO_A7") (class "Default")
      (node (ref "U$19") (pin "0") (pinfunction "0_0") (pintype "bidirectional"))
      (node (ref "U4") (pin "28") (pinfunction "GPA7_28") (pintype "bidirectional"))
    )
    (net (code "33") (name "GPIO_B6") (class "Default")
      (node (ref "U$14") (pin "0") (pinfunction "0_0") (pintype "bidirectional"))
      (node (ref "U4") (pin "7") (pinfunction "GPB6_7") (pintype "bidirectional"))
    )
    (net (code "34") (name "GPIO_B7") (class "Default")
      (node (ref "U$20") (pin "0") (pinfunction "0_0") (pintype "bidirectional"))
      (node (ref "U4") (pin "8") (pinfunction "GPB7_8") (pintype "bidirectional"))
    )
    (net (code "35") (name "GPS_RX") (class "Default")
      (node (ref "A1") (pin "8") (pinfunction "IO32_8") (pintype "bidirectional"))
      (node (ref "IC1") (pin "3") (pinfunction "RX_3") (pintype "bidirectional"))
      (node (ref "U$11") (pin "0") (pinfunction "0_0") (pintype "bidirectional"))
    )
    (net (code "36") (name "GPS_TX") (class "Default")
      (node (ref "A1") (pin "9") (pinfunction "IO33_9") (pintype "bidirectional"))
      (node (ref "IC1") (pin "2") (pinfunction "TX_2") (pintype "bidirectional"))
      (node (ref "U$12") (pin "0") (pinfunction "0_0") (pintype "bidirectional"))
    )
    (net (code "37") (name "I2C_SCL") (class "Default")
      (node (ref "A1") (pin "36") (pinfunction "IO22_36") (pintype "bidirectional"))
      (node (ref "R19") (pin "2") (pinfunction "2_2") (pintype "passive"))
      (node (ref "U$1") (pin "23") (pinfunction "SCL/SCLK_23") (pintype "bidirectional"))
      (node (ref "U$10") (pin "0") (pinfunction "0_0") (pintype "bidirectional"))
      (node (ref "U$5") (pin "4") (pinfunction "SCK_4") (pintype "bidirectional"))
      (node (ref "U2") (pin "4") (pinfunction "SCL/SCLK_4") (pintype "input"))
      (node (ref "U4") (pin "12") (pinfunction "SCK_12") (pintype "input"))
    )
    (net (code "38") (name "I2C_SDA") (class "Default")
      (node (ref "A1") (pin "33") (pinfunction "IO21_33") (pintype "bidirectional"))
      (node (ref "R18") (pin "2") (pinfunction "2_2") (pintype "passive"))
      (node (ref "U$1") (pin "24") (pinfunction "SDA/SDI_24") (pintype "bidirectional"))
      (node (ref "U$5") (pin "3") (pinfunction "SDA_3") (pintype "bidirectional"))
      (node (ref "U$9") (pin "0") (pinfunction "0_0") (pintype "bidirectional"))
      (node (ref "U2") (pin "6") (pinfunction "SDA/MOSI_6") (pintype "bidirectional"))
      (node (ref "U4") (pin "13") (pinfunction "SDA_13") (pintype "bidirectional"))
    )
    (net (code "39") (name "JTAG_TCK") (class "Default")
      (node (ref "A1") (pin "16") (pinfunction "IO13_16") (pintype "bidirectional"))
      (node (ref "R9") (pin "1") (pinfunction "1_1") (pintype "passive"))
      (node (ref "U$6") (pin "4") (pinfunction "ESP_TCK_4") (pintype "bidirectional"))
    )
    (net (code "40") (name "JTAG_TDI") (class "Default")
      (node (ref "A1") (pin "14") (pinfunction "IO12_14") (pintype "bidirectional"))
      (node (ref "R10") (pin "1") (pinfunction "1_1") (pintype "passive"))
      (node (ref "U$6") (pin "8") (pinfunction "ESP_TDI_8") (pintype "bidirectional"))
    )
    (net (code "41") (name "JTAG_TDO") (class "Default")
      (node (ref "A1") (pin "23") (pinfunction "IO15_23") (pintype "bidirectional"))
      (node (ref "R11") (pin "1") (pinfunction "1_1") (pintype "passive"))
      (node (ref "U$6") (pin "6") (pinfunction "ESP_TDO_6") (pintype "bidirectional"))
    )
    (net (code "42") (name "JTAG_TMS") (class "Default")
      (node (ref "A1") (pin "13") (pinfunction "IO14_13") (pintype "bidirectional"))
      (node (ref "R8") (pin "1") (pinfunction "1_1") (pintype "passive"))
      (node (ref "U$6") (pin "2") (pinfunction "ESP_TMS_2") (pintype "bidirectional"))
    )
    (net (code "43") (name "LED_B") (class "Default")
      (node (ref "D2") (pin "6") (pinfunction "6_6") (pintype "passive"))
      (node (ref "U4") (pin "21") (pinfunction "GPA0_21") (pintype "bidirectional"))
    )
    (net (code "44") (name "LED_G") (class "Default")
      (node (ref "D2") (pin "5") (pinfunction "5_5") (pintype "passive"))
      (node (ref "U4") (pin "22") (pinfunction "GPA1_22") (pintype "bidirectional"))
    )
    (net (code "45") (name "LED_R") (class "Default")
      (node (ref "D2") (pin "4") (pinfunction "4_4") (pintype "passive"))
      (node (ref "U4") (pin "23") (pinfunction "GPA2_23") (pintype "bidirectional"))
    )
    (net (code "46") (name "Net-(D2-Pad1)") (class "Default")
      (node (ref "D2") (pin "1") (pinfunction "1_1") (pintype "passive"))
      (node (ref "LEDB") (pin "1") (pinfunction "1_1") (pintype "passive"))
    )
    (net (code "47") (name "Net-(D2-Pad2)") (class "Default")
      (node (ref "D2") (pin "2") (pinfunction "2_2") (pintype "passive"))
      (node (ref "LEDG") (pin "1") (pinfunction "1_1") (pintype "passive"))
    )
    (net (code "48") (name "Net-(D2-Pad3)") (class "Default")
      (node (ref "D2") (pin "3") (pinfunction "3_3") (pintype "passive"))
      (node (ref "LEDR") (pin "1") (pinfunction "1_1") (pintype "passive"))
    )
    (net (code "49") (name "Net-(IC1-RF_IN)") (class "Default")
      (node (ref "C22") (pin "1") (pinfunction "1_1") (pintype "passive"))
      (node (ref "IC1") (pin "11") (pinfunction "RF_IN_11") (pintype "bidirectional"))
    )
    (net (code "50") (name "Net-(PWR-INDICATOR--)") (class "Default")
      (node (ref "PWR-INDICATOR") (pin "1") (pinfunction "-_1") (pintype "bidirectional"))
      (node (ref "R3") (pin "1") (pinfunction "1_1") (pintype "passive"))
    )
    (net (code "51") (name "Net-(U$1-REGOUT)") (class "Default")
      (node (ref "C1") (pin "2") (pinfunction "2_2") (pintype "passive"))
      (node (ref "U$1") (pin "10") (pinfunction "REGOUT_10") (pintype "bidirectional"))
    )
    (net (code "52") (name "Net-(U2-BYP)") (class "Default")
      (node (ref "C25") (pin "1") (pinfunction "1_1") (pintype "passive"))
      (node (ref "U2") (pin "2") (pinfunction "BYP_2") (pintype "output"))
    )
    (net (code "53") (name "Net-(U2-CRST)") (class "Default")
      (node (ref "C26") (pin "1") (pinfunction "1_1") (pintype "passive"))
      (node (ref "U2") (pin "8") (pinfunction "CRST_8") (pintype "bidirectional"))
    )
    (net (code "54") (name "Net-(U4-~{RESET})") (class "Default")
      (node (ref "R15") (pin "1") (pinfunction "1_1") (pintype "passive"))
      (node (ref "U4") (pin "18") (pinfunction "~{RESET}_18") (pintype "input"))
    )
    (net (code "55") (name "PROGRAM_EN") (class "Default")
      (node (ref "A1") (pin "3") (pinfunction "EN_3") (pintype "input"))
      (node (ref "C11") (pin "2") (pinfunction "2_2") (pintype "passive"))
      (node (ref "R7") (pin "1") (pinfunction "1_1") (pintype "passive"))
      (node (ref "U$23") (pin "0") (pinfunction "0_0") (pintype "bidirectional"))
      (node (ref "U$7") (pin "1") (pinfunction "ESP_EN_1") (pintype "bidirectional"))
      (node (ref "U$8") (pin "B") (pinfunction "B_B") (pintype "bidirectional"))
      (node (ref "U$8") (pin "B@1") (pinfunction "B_B@1") (pintype "bidirectional"))
    )
    (net (code "56") (name "PROGRAM_IO0") (class "Default")
      (node (ref "A1") (pin "25") (pinfunction "IO0_25") (pintype "bidirectional"))
      (node (ref "R14") (pin "1") (pinfunction "1_1") (pintype "passive"))
      (node (ref "U$7") (pin "6") (pinfunction "ESP_IO0_6") (pintype "bidirectional"))
    )
    (net (code "57") (name "PROGRAM_RX") (class "Default")
      (node (ref "A1") (pin "34") (pinfunction "RXD0_34") (pintype "bidirectional"))
      (node (ref "R17") (pin "2") (pinfunction "2_2") (pintype "passive"))
      (node (ref "U$7") (pin "5") (pinfunction "ESP_RXD_5") (pintype "bidirectional"))
    )
    (net (code "58") (name "PROGRAM_TX") (class "Default")
      (node (ref "A1") (pin "35") (pinfunction "TXD0_35") (pintype "bidirectional"))
      (node (ref "R16") (pin "2") (pinfunction "2_2") (pintype "passive"))
      (node (ref "U$7") (pin "3") (pinfunction "ESP_TXD_3") (pintype "bidirectional"))
    )
    (net (code "59") (name "SD_CD") (class "Default")
      (node (ref "U$3") (pin "10") (pinfunction "CD_10") (pintype "bidirectional"))
      (node (ref "U4") (pin "26") (pinfunction "GPA5_26") (pintype "bidirectional"))
    )
    (net (code "60") (name "SD_CLK") (class "Default")
      (node (ref "R8") (pin "2") (pinfunction "2_2") (pintype "passive"))
      (node (ref "U$3") (pin "5") (pinfunction "CLK_5") (pintype "bidirectional"))
    )
    (net (code "61") (name "SD_CMD") (class "Default")
      (node (ref "R11") (pin "2") (pinfunction "2_2") (pintype "passive"))
      (node (ref "R12") (pin "2") (pinfunction "2_2") (pintype "passive"))
      (node (ref "U$3") (pin "2") (pinfunction "CMD_2") (pintype "bidirectional"))
    )
    (net (code "62") (name "SD_DAT0") (class "Default")
      (node (ref "A1") (pin "24") (pinfunction "IO2_24") (pintype "bidirectional"))
      (node (ref "R13") (pin "2") (pinfunction "2_2") (pintype "passive"))
      (node (ref "U$3") (pin "7") (pinfunction "DAT0_7") (pintype "bidirectional"))
    )
    (net (code "63") (name "SD_DAT1") (class "Default")
      (node (ref "A1") (pin "26") (pinfunction "IO4_26") (pintype "bidirectional"))
      (node (ref "U$3") (pin "8") (pinfunction "DAT1_8") (pintype "bidirectional"))
    )
    (net (code "64") (name "SD_DAT2") (class "Default")
      (node (ref "R10") (pin "2") (pinfunction "2_2") (pintype "passive"))
      (node (ref "U$3") (pin "9") (pinfunction "DAT2_9") (pintype "bidirectional"))
    )
    (net (code "65") (name "SD_DAT3") (class "Default")
      (node (ref "R9") (pin "2") (pinfunction "2_2") (pintype "passive"))
      (node (ref "U$3") (pin "1") (pinfunction "CD/DAT3_1") (pintype "bidirectional"))
    )
    (net (code "66") (name "SD_WP") (class "Default")
      (node (ref "U$3") (pin "11") (pinfunction "WP_11") (pintype "bidirectional"))
      (node (ref "U4") (pin "25") (pinfunction "GPA4_25") (pintype "bidirectional"))
    )
    (net (code "67") (name "VBAT") (class "Default")
      (node (ref "C12") (pin "2") (pinfunction "2_2") (pintype "passive"))
      (node (ref "C13") (pin "2") (pinfunction "2_2") (pintype "passive"))
      (node (ref "PS1") (pin "1") (pinfunction "+VIN_1") (pintype "input"))
      (node (ref "U$13") (pin "0") (pinfunction "0_0") (pintype "bidirectional"))
      (node (ref "U$28") (pin "3") (pinfunction "INPUT_3") (pintype "bidirectional"))
      (node (ref "U$29") (pin "V_BAT") (pinfunction "V_BAT_V_BAT") (pintype "bidirectional"))
    )
    (net (code "68") (name "VCC_RF") (class "Default")
      (node (ref "C23") (pin "2") (pinfunction "2_2") (pintype "passive"))
      (node (ref "IC1") (pin "14") (pinfunction "VCC_RF_14") (pintype "bidirectional"))
      (node (ref "L1") (pin "1") (pinfunction "1_1") (pintype "passive"))
    )
    (net (code "69") (name "XMCLK") (class "Default")
      (node (ref "A1") (pin "11") (pinfunction "IO26_11") (pintype "bidirectional"))
      (node (ref "J1") (pin "13") (pinfunction "13_13") (pintype "bidirectional"))
    )
    (net (code "70") (name "unconnected-(A1-SCK{slash}CLK-Pad20)") (class "Default")
      (node (ref "A1") (pin "20") (pinfunction "SCK/CLK_20") (pintype "bidirectional"))
    )
    (net (code "71") (name "unconnected-(A1-SCS{slash}CMD-Pad19)") (class "Default")
      (node (ref "A1") (pin "19") (pinfunction "SCS/CMD_19") (pintype "bidirectional"))
    )
    (net (code "72") (name "unconnected-(A1-SDI{slash}SD1-Pad22)") (class "Default")
      (node (ref "A1") (pin "22") (pinfunction "SDI/SD1_22") (pintype "bidirectional"))
    )
    (net (code "73") (name "unconnected-(A1-SDO{slash}SD0-Pad21)") (class "Default")
      (node (ref "A1") (pin "21") (pinfunction "SDO/SD0_21") (pintype "bidirectional"))
    )
    (net (code "74") (name "unconnected-(A1-SHD{slash}SD2-Pad17)") (class "Default")
      (node (ref "A1") (pin "17") (pinfunction "SHD/SD2_17") (pintype "bidirectional"))
    )
    (net (code "75") (name "unconnected-(A1-SWP{slash}SD3-Pad18)") (class "Default")
      (node (ref "A1") (pin "18") (pinfunction "SWP/SD3_18") (pintype "bidirectional"))
    )
    (net (code "76") (name "unconnected-(IC1-1PPS-Pad4)") (class "Default")
      (node (ref "IC1") (pin "4") (pinfunction "1PPS_4") (pintype "bidirectional"))
    )
    (net (code "77") (name "unconnected-(IC1-ANT_OFF-Pad13)") (class "Default")
      (node (ref "IC1") (pin "13") (pinfunction "ANT_OFF_13") (pintype "bidirectional"))
    )
    (net (code "78") (name "unconnected-(IC1-RESERVED_1-Pad15)") (class "Default")
      (node (ref "IC1") (pin "15") (pinfunction "RESERVED_1_15") (pintype "bidirectional"))
    )
    (net (code "79") (name "unconnected-(IC1-RESERVED_2-Pad18)") (class "Default")
      (node (ref "IC1") (pin "18") (pinfunction "RESERVED_2_18") (pintype "bidirectional"))
    )
    (net (code "80") (name "unconnected-(IC1-SCL-Pad17)") (class "Default")
      (node (ref "IC1") (pin "17") (pinfunction "SCL_17") (pintype "bidirectional"))
    )
    (net (code "81") (name "unconnected-(IC1-SDA-Pad16)") (class "Default")
      (node (ref "IC1") (pin "16") (pinfunction "SDA_16") (pintype "bidirectional"))
    )
    (net (code "82") (name "unconnected-(IC1-SYS_RSTN-Pad9)") (class "Default")
      (node (ref "IC1") (pin "9") (pinfunction "SYS_RSTN_9") (pintype "bidirectional"))
    )
    (net (code "83") (name "unconnected-(IC1-WAKE-UP-Pad5)") (class "Default")
      (node (ref "IC1") (pin "5") (pinfunction "WAKE-UP_5") (pintype "bidirectional"))
    )
    (net (code "84") (name "unconnected-(J1-Pad1)") (class "Default")
      (node (ref "J1") (pin "1") (pinfunction "1_1") (pintype "bidirectional"))
    )
    (net (code "85") (name "unconnected-(J1-Pad23)") (class "Default")
      (node (ref "J1") (pin "23") (pinfunction "23_23") (pintype "bidirectional"))
    )
    (net (code "86") (name "unconnected-(J1-Pad24)") (class "Default")
      (node (ref "J1") (pin "24") (pinfunction "24_24") (pintype "bidirectional"))
    )
    (net (code "87") (name "unconnected-(U$1-AUX_CL-Pad7)") (class "Default")
      (node (ref "U$1") (pin "7") (pinfunction "AUX_CL_7") (pintype "bidirectional"))
    )
    (net (code "88") (name "unconnected-(U$1-AUX_DA-Pad21)") (class "Default")
      (node (ref "U$1") (pin "21") (pinfunction "AUX_DA_21") (pintype "bidirectional"))
    )
    (net (code "89") (name "unconnected-(U$1-INT-Pad12)") (class "Default")
      (node (ref "U$1") (pin "12") (pinfunction "INT_12") (pintype "bidirectional"))
    )
    (net (code "90") (name "unconnected-(U$5-CSB-Pad2)") (class "Default")
      (node (ref "U$5") (pin "2") (pinfunction "CSB_2") (pintype "bidirectional"))
    )
    (net (code "91") (name "unconnected-(U$5-SDO-Pad5)") (class "Default")
      (node (ref "U$5") (pin "5") (pinfunction "SDO_5") (pintype "bidirectional"))
    )
    (net (code "92") (name "unconnected-(U2-INT1-Pad11)") (class "Default")
      (node (ref "U2") (pin "11") (pinfunction "INT1_11") (pintype "bidirectional"))
    )
    (net (code "93") (name "unconnected-(U2-INT2-Pad9)") (class "Default")
      (node (ref "U2") (pin "9") (pinfunction "INT2_9") (pintype "bidirectional"))
    )
    (net (code "94") (name "unconnected-(U2-NC-Pad15)") (class "Default")
      (node (ref "U2") (pin "15") (pinfunction "NC_15") (pintype "no_connect"))
    )
    (net (code "95") (name "unconnected-(U3-NC-Pad12)") (class "Default")
      (node (ref "U3") (pin "12") (pinfunction "NC_12") (pintype "input"))
    )
    (net (code "96") (name "unconnected-(U4-INTA-Pad20)") (class "Default")
      (node (ref "U4") (pin "20") (pinfunction "INTA_20") (pintype "output"))
    )
    (net (code "97") (name "unconnected-(U4-INTB-Pad19)") (class "Default")
      (node (ref "U4") (pin "19") (pinfunction "INTB_19") (pintype "output"))
    )
    (net (code "98") (name "unconnected-(U5-NC-Pad4)") (class "Default")
      (node (ref "U5") (pin "4") (pinfunction "NC_4") (pintype "input"))
    )
    (net (code "99") (name "unconnected-(U6-NC-Pad4)") (class "Default")
      (node (ref "U6") (pin "4") (pinfunction "NC_4") (pintype "no_connect"))
    )
  )
)
